# VIDEO_IN_TVP5150.net
KiCad netlist of a schematic drawn in Altium Designer
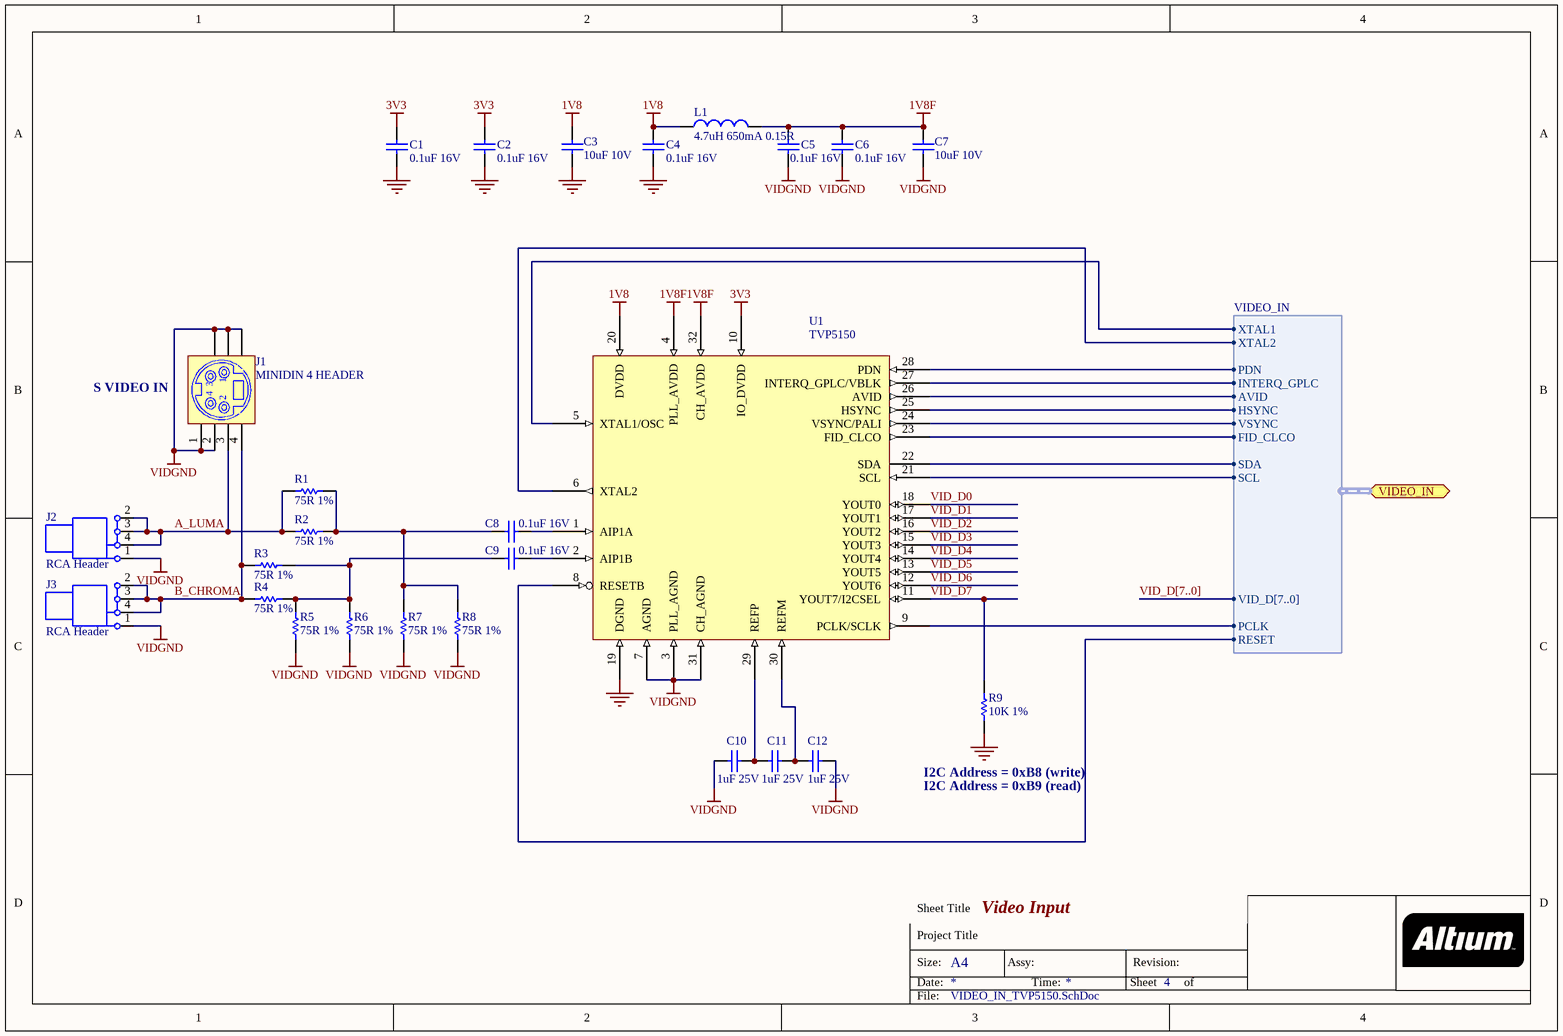
[diagram p0: VIDEO_IN_TVP5150.SchDoc]

(export (version "E")
  (design (tool "Eeschema 10.0.6"))
  (components
    (comp (ref "C1")
      (value "0.1uF 16V")
      (footprint "CAPC1005-STAR")
      (description "Capacitor, Ceramic, 0.1uF 10% 16V 0402 (1005) X7R")
      (fields (field (name "TOLERANCE") "10 %"))
      (libsource (lib "AltiumDesignLibrary") (part "CAP-NP"))
    )
    (comp (ref "C2")
      (value "0.1uF 16V")
      (footprint "CAPC1005-STAR")
      (description "Capacitor, Ceramic, 0.1uF 10% 16V 0402 (1005) X7R")
      (fields (field (name "TOLERANCE") "10 %"))
      (libsource (lib "AltiumDesignLibrary") (part "CAP-NP"))
    )
    (comp (ref "C3")
      (value "10uF 10V")
      (footprint "CAPC2012-STAR")
      (description "Capacitor, Ceramic, 10uF 10% 10V 0805 (2012) X5R")
      (fields (field (name "TOLERANCE") "10 %"))
      (libsource (lib "AltiumDesignLibrary") (part "CAP-NP"))
    )
    (comp (ref "C4")
      (value "0.1uF 16V")
      (footprint "CAPC1005-STAR")
      (description "Capacitor, Ceramic, 0.1uF 10% 16V 0402 (1005) X7R")
      (fields (field (name "TOLERANCE") "10 %"))
      (libsource (lib "AltiumDesignLibrary") (part "CAP-NP"))
    )
    (comp (ref "C5")
      (value "0.1uF 16V")
      (footprint "CAPC1005-STAR")
      (description "Capacitor, Ceramic, 0.1uF 10% 16V 0402 (1005) X7R")
      (fields (field (name "TOLERANCE") "10 %"))
      (libsource (lib "AltiumDesignLibrary") (part "CAP-NP"))
    )
    (comp (ref "C6")
      (value "0.1uF 16V")
      (footprint "CAPC1005-STAR")
      (description "Capacitor, Ceramic, 0.1uF 10% 16V 0402 (1005) X7R")
      (fields (field (name "TOLERANCE") "10 %"))
      (libsource (lib "AltiumDesignLibrary") (part "CAP-NP"))
    )
    (comp (ref "C7")
      (value "10uF 10V")
      (footprint "CAPC2012-STAR")
      (description "Capacitor, Ceramic, 10uF 10% 10V 0805 (2012) X5R")
      (fields (field (name "TOLERANCE") "10 %"))
      (libsource (lib "AltiumDesignLibrary") (part "CAP-NP"))
    )
    (comp (ref "C8")
      (value "0.1uF 16V")
      (footprint "CAPC1005-STAR")
      (description "Capacitor, Ceramic, 0.1uF 10% 16V 0402 (1005) X7R")
      (fields (field (name "TOLERANCE") "10 %"))
      (libsource (lib "AltiumDesignLibrary") (part "CAP-NP"))
    )
    (comp (ref "C9")
      (value "0.1uF 16V")
      (footprint "CAPC1005-STAR")
      (description "Capacitor, Ceramic, 0.1uF 10% 16V 0402 (1005) X7R")
      (fields (field (name "TOLERANCE") "10 %"))
      (libsource (lib "AltiumDesignLibrary") (part "CAP-NP"))
    )
    (comp (ref "C10")
      (value "1uF 25V")
      (footprint "CAPC3216-STAR")
      (description "Capacitor, Ceramic, 1uF 10% 25V 1206 (3216) X7R")
      (fields (field (name "TOLERANCE") "10 %"))
      (libsource (lib "AltiumDesignLibrary") (part "CAP-NP"))
    )
    (comp (ref "C11")
      (value "1uF 25V")
      (footprint "CAPC3216-STAR")
      (description "Capacitor, Ceramic, 1uF 10% 25V 1206 (3216) X7R")
      (fields (field (name "TOLERANCE") "10 %"))
      (libsource (lib "AltiumDesignLibrary") (part "CAP-NP"))
    )
    (comp (ref "C12")
      (value "1uF 25V")
      (footprint "CAPC3216-STAR")
      (description "Capacitor, Ceramic, 1uF 10% 25V 1206 (3216) X7R")
      (fields (field (name "TOLERANCE") "10 %"))
      (libsource (lib "AltiumDesignLibrary") (part "CAP-NP"))
    )
    (comp (ref "J1")
      (value "MINIDIN 4 HEADER")
      (footprint "MDJ-F-04")
      (description "Connector, 4850.241, Mini-DIN 4-Way, S-Video/Yellow")
      (libsource (lib "AltiumDesignLibrary") (part "CON-MINIDIN-4-F"))
    )
    (comp (ref "J2")
      (value "RCA Header")
      (footprint "TRC-005")
      (description "Connector, TRC-005-4 , RCA Phono Jack, Right Angle, Thru-Hole, Snap-In")
      (libsource (lib "AltiumDesignLibrary") (part "CON-RCA-RA"))
    )
    (comp (ref "J3")
      (value "RCA Header")
      (footprint "TRC-005")
      (description "Connector, TRC-005-4 , RCA Phono Jack, Right Angle, Thru-Hole, Snap-In")
      (libsource (lib "AltiumDesignLibrary") (part "CON-RCA-RA"))
    )
    (comp (ref "L1")
      (value "4.7uH 650mA 0.15R")
      (footprint "INDC3225")
      (description "Inductor, 4.7uH 650mA 0.15R 1210 (3225) LQH32CN4R7M11L")
      (libsource (lib "AltiumDesignLibrary") (part "IND"))
    )
    (comp (ref "R1")
      (value "75R 1%")
      (footprint "RESC1005-STAR")
      (description "Resistor, 75R 1% 0402")
      (fields (field (name "TOLERANCE") "1 %"))
      (libsource (lib "AltiumDesignLibrary") (part "RES"))
    )
    (comp (ref "R2")
      (value "75R 1%")
      (footprint "RESC1005-STAR")
      (description "Resistor, 75R 1% 0402")
      (fields (field (name "TOLERANCE") "1 %"))
      (libsource (lib "AltiumDesignLibrary") (part "RES"))
    )
    (comp (ref "R3")
      (value "75R 1%")
      (footprint "RESC1005-STAR")
      (description "Resistor, 75R 1% 0402")
      (fields (field (name "TOLERANCE") "1 %"))
      (libsource (lib "AltiumDesignLibrary") (part "RES"))
    )
    (comp (ref "R4")
      (value "75R 1%")
      (footprint "RESC1005-STAR")
      (description "Resistor, 75R 1% 0402")
      (fields (field (name "TOLERANCE") "1 %"))
      (libsource (lib "AltiumDesignLibrary") (part "RES"))
    )
    (comp (ref "R5")
      (value "75R 1%")
      (footprint "RESC1005-STAR")
      (description "Resistor, 75R 1% 0402")
      (fields (field (name "TOLERANCE") "1 %"))
      (libsource (lib "AltiumDesignLibrary") (part "RES"))
    )
    (comp (ref "R6")
      (value "75R 1%")
      (footprint "RESC1005-STAR")
      (description "Resistor, 75R 1% 0402")
      (fields (field (name "TOLERANCE") "1 %"))
      (libsource (lib "AltiumDesignLibrary") (part "RES"))
    )
    (comp (ref "R7")
      (value "75R 1%")
      (footprint "RESC1005-STAR")
      (description "Resistor, 75R 1% 0402")
      (fields (field (name "TOLERANCE") "1 %"))
      (libsource (lib "AltiumDesignLibrary") (part "RES"))
    )
    (comp (ref "R8")
      (value "75R 1%")
      (footprint "RESC1005-STAR")
      (description "Resistor, 75R 1% 0402")
      (fields (field (name "TOLERANCE") "1 %"))
      (libsource (lib "AltiumDesignLibrary") (part "RES"))
    )
    (comp (ref "R9")
      (value "10K 1%")
      (footprint "RESC1005-STAR")
      (description "Resistor, 10K 1% 0402 (1005)")
      (fields (field (name "TOLERANCE") "1 %"))
      (libsource (lib "AltiumDesignLibrary") (part "RES"))
    )
    (comp (ref "U1")
      (value "TVP5150")
      (footprint "TSQFP50P700X700-32")
      (description "TVP5150AM1PBS, Ultralow Power NTSC/PAL/SECAM Video Decoder With Robust Sync Detector")
      (libsource (lib "AltiumDesignLibrary") (part "TVP5150"))
    )
  )
  (nets
    (net (code "2") (name "/AVID") (class "Default")
      (node (ref "U1") (pin "26") (pinfunction "AVID_26") (pintype "output"))
    )
    (net (code "3") (name "/A_LUMA") (class "Default")
      (node (ref "J1") (pin "3") (pinfunction "H_3") (pintype "passive"))
      (node (ref "J2") (pin "2") (pinfunction "Yellow_2") (pintype "passive"))
      (node (ref "J2") (pin "3") (pinfunction "White_3") (pintype "passive"))
      (node (ref "J2") (pin "4") (pinfunction "Red_4") (pintype "passive"))
      (node (ref "R1") (pin "2") (pinfunction "2_2") (pintype "passive"))
      (node (ref "R2") (pin "2") (pinfunction "2_2") (pintype "passive"))
    )
    (net (code "4") (name "/B_CHROMA") (class "Default")
      (node (ref "J1") (pin "4") (pinfunction "E_4") (pintype "passive"))
      (node (ref "J3") (pin "2") (pinfunction "Yellow_2") (pintype "passive"))
      (node (ref "J3") (pin "3") (pinfunction "White_3") (pintype "passive"))
      (node (ref "J3") (pin "4") (pinfunction "Red_4") (pintype "passive"))
      (node (ref "R3") (pin "2") (pinfunction "2_2") (pintype "passive"))
      (node (ref "R4") (pin "1") (pinfunction "1_1") (pintype "passive"))
    )
    (net (code "5") (name "/FID_CLCO") (class "Default")
      (node (ref "U1") (pin "23") (pinfunction "FID_CLCO_23") (pintype "output"))
    )
    (net (code "6") (name "/HSYNC") (class "Default")
      (node (ref "U1") (pin "25") (pinfunction "HSYNC_25") (pintype "output"))
    )
    (net (code "7") (name "/INTERQ_GPLC") (class "Default")
      (node (ref "U1") (pin "27") (pinfunction "INTERQ_GPLC/VBLK_27") (pintype "output"))
    )
    (net (code "8") (name "/PCLK") (class "Default")
      (node (ref "U1") (pin "9") (pinfunction "PCLK/SCLK_9") (pintype "output"))
    )
    (net (code "9") (name "/PDN") (class "Default")
      (node (ref "U1") (pin "28") (pinfunction "PDN_28") (pintype "input"))
    )
    (net (code "10") (name "/RESET") (class "Default")
      (node (ref "U1") (pin "8") (pinfunction "RESETB_8") (pintype "input"))
    )
    (net (code "11") (name "/SCL") (class "Default")
      (node (ref "U1") (pin "21") (pinfunction "SCL_21") (pintype "input"))
    )
    (net (code "12") (name "/SDA") (class "Default")
      (node (ref "U1") (pin "22") (pinfunction "SDA_22") (pintype "open_collector"))
    )
    (net (code "13") (name "/VID_D0") (class "Default")
      (node (ref "U1") (pin "18") (pinfunction "YOUT0_18") (pintype "bidirectional"))
    )
    (net (code "14") (name "/VID_D1") (class "Default")
      (node (ref "U1") (pin "17") (pinfunction "YOUT1_17") (pintype "bidirectional"))
    )
    (net (code "15") (name "/VID_D2") (class "Default")
      (node (ref "U1") (pin "16") (pinfunction "YOUT2_16") (pintype "bidirectional"))
    )
    (net (code "16") (name "/VID_D3") (class "Default")
      (node (ref "U1") (pin "15") (pinfunction "YOUT3_15") (pintype "bidirectional"))
    )
    (net (code "17") (name "/VID_D4") (class "Default")
      (node (ref "U1") (pin "14") (pinfunction "YOUT4_14") (pintype "bidirectional"))
    )
    (net (code "18") (name "/VID_D5") (class "Default")
      (node (ref "U1") (pin "13") (pinfunction "YOUT5_13") (pintype "bidirectional"))
    )
    (net (code "19") (name "/VID_D6") (class "Default")
      (node (ref "U1") (pin "12") (pinfunction "YOUT6_12") (pintype "bidirectional"))
    )
    (net (code "20") (name "/VID_D7") (class "Default")
      (node (ref "R9") (pin "2") (pinfunction "2_2") (pintype "passive"))
      (node (ref "U1") (pin "11") (pinfunction "YOUT7/I2CSEL_11") (pintype "bidirectional"))
    )
    (net (code "22") (name "/VSYNC") (class "Default")
      (node (ref "U1") (pin "24") (pinfunction "VSYNC/PALI_24") (pintype "output"))
    )
    (net (code "23") (name "/XTAL1") (class "Default")
      (node (ref "U1") (pin "5") (pinfunction "XTAL1/OSC_5") (pintype "input"))
    )
    (net (code "24") (name "/XTAL2") (class "Default")
      (node (ref "U1") (pin "6") (pinfunction "XTAL2_6") (pintype "output"))
    )
    (net (code "26") (name "1V8") (class "Default")
      (node (ref "C3") (pin "1") (pinfunction "1_1") (pintype "passive"))
      (node (ref "C4") (pin "2") (pinfunction "2_2") (pintype "passive"))
      (node (ref "L1") (pin "2") (pinfunction "2_2") (pintype "passive"))
      (node (ref "U1") (pin "20") (pinfunction "DVDD_20") (pintype "input"))
    )
    (net (code "27") (name "1V8F") (class "Default")
      (node (ref "C5") (pin "2") (pinfunction "2_2") (pintype "passive"))
      (node (ref "C6") (pin "2") (pinfunction "2_2") (pintype "passive"))
      (node (ref "C7") (pin "1") (pinfunction "1_1") (pintype "passive"))
      (node (ref "L1") (pin "1") (pinfunction "1_1") (pintype "passive"))
      (node (ref "U1") (pin "32") (pinfunction "CH_AVDD_32") (pintype "input"))
      (node (ref "U1") (pin "4") (pinfunction "PLL_AVDD_4") (pintype "input"))
    )
    (net (code "28") (name "3V3") (class "Default")
      (node (ref "C1") (pin "2") (pinfunction "2_2") (pintype "passive"))
      (node (ref "C2") (pin "2") (pinfunction "2_2") (pintype "passive"))
      (node (ref "U1") (pin "10") (pinfunction "IO_DVDD_10") (pintype "input"))
    )
    (net (code "29") (name "GND") (class "Default")
      (node (ref "C1") (pin "1") (pinfunction "1_1") (pintype "passive"))
      (node (ref "C2") (pin "1") (pinfunction "1_1") (pintype "passive"))
      (node (ref "C3") (pin "2") (pinfunction "2_2") (pintype "passive"))
      (node (ref "C4") (pin "1") (pinfunction "1_1") (pintype "passive"))
      (node (ref "R9") (pin "1") (pinfunction "1_1") (pintype "passive"))
      (node (ref "U1") (pin "19") (pinfunction "DGND_19") (pintype "input"))
    )
    (net (code "30") (name "Net-(C8-Pad1)") (class "Default")
      (node (ref "C8") (pin "1") (pinfunction "1_1") (pintype "passive"))
      (node (ref "R1") (pin "1") (pinfunction "1_1") (pintype "passive"))
      (node (ref "R2") (pin "1") (pinfunction "1_1") (pintype "passive"))
      (node (ref "R7") (pin "2") (pinfunction "2_2") (pintype "passive"))
      (node (ref "R8") (pin "2") (pinfunction "2_2") (pintype "passive"))
    )
    (net (code "31") (name "Net-(C9-Pad1)") (class "Default")
      (node (ref "C9") (pin "1") (pinfunction "1_1") (pintype "passive"))
      (node (ref "R3") (pin "1") (pinfunction "1_1") (pintype "passive"))
      (node (ref "R4") (pin "2") (pinfunction "2_2") (pintype "passive"))
      (node (ref "R5") (pin "2") (pinfunction "2_2") (pintype "passive"))
      (node (ref "R6") (pin "2") (pinfunction "2_2") (pintype "passive"))
    )
    (net (code "32") (name "Net-(U1-AIP1A)") (class "Default")
      (node (ref "C8") (pin "2") (pinfunction "2_2") (pintype "passive"))
      (node (ref "U1") (pin "1") (pinfunction "AIP1A_1") (pintype "input"))
    )
    (net (code "33") (name "Net-(U1-AIP1B)") (class "Default")
      (node (ref "C9") (pin "2") (pinfunction "2_2") (pintype "passive"))
      (node (ref "U1") (pin "2") (pinfunction "AIP1B_2") (pintype "input"))
    )
    (net (code "34") (name "Net-(U1-REFM)") (class "Default")
      (node (ref "C11") (pin "1") (pinfunction "1_1") (pintype "passive"))
      (node (ref "C12") (pin "2") (pinfunction "2_2") (pintype "passive"))
      (node (ref "U1") (pin "30") (pinfunction "REFM_30") (pintype "input"))
    )
    (net (code "35") (name "Net-(U1-REFP)") (class "Default")
      (node (ref "C10") (pin "1") (pinfunction "1_1") (pintype "passive"))
      (node (ref "C11") (pin "2") (pinfunction "2_2") (pintype "passive"))
      (node (ref "U1") (pin "29") (pinfunction "REFP_29") (pintype "input"))
    )
    (net (code "36") (name "VIDGND") (class "Default")
      (node (ref "C10") (pin "2") (pinfunction "2_2") (pintype "passive"))
      (node (ref "C12") (pin "1") (pinfunction "1_1") (pintype "passive"))
      (node (ref "C5") (pin "1") (pinfunction "1_1") (pintype "passive"))
      (node (ref "C6") (pin "1") (pinfunction "1_1") (pintype "passive"))
      (node (ref "C7") (pin "2") (pinfunction "2_2") (pintype "passive"))
      (node (ref "J1") (pin "1") (pinfunction "D_1") (pintype "passive"))
      (node (ref "J1") (pin "2") (pinfunction "A_2") (pintype "passive"))
      (node (ref "J1") (pin "MH1") (pinfunction "MH1_MH1") (pintype "passive"))
      (node (ref "J1") (pin "MH2") (pinfunction "MH2_MH2") (pintype "passive"))
      (node (ref "J1") (pin "MH3") (pinfunction "MH3_MH3") (pintype "passive"))
      (node (ref "J2") (pin "1") (pinfunction "Black_1") (pintype "passive"))
      (node (ref "J3") (pin "1") (pinfunction "Black_1") (pintype "passive"))
      (node (ref "R5") (pin "1") (pinfunction "1_1") (pintype "passive"))
      (node (ref "R6") (pin "1") (pinfunction "1_1") (pintype "passive"))
      (node (ref "R7") (pin "1") (pinfunction "1_1") (pintype "passive"))
      (node (ref "R8") (pin "1") (pinfunction "1_1") (pintype "passive"))
      (node (ref "U1") (pin "3") (pinfunction "PLL_AGND_3") (pintype "input"))
      (node (ref "U1") (pin "31") (pinfunction "CH_AGND_31") (pintype "input"))
      (node (ref "U1") (pin "7") (pinfunction "AGND_7") (pintype "input"))
    )
  )
)
